# SkyKontrol-powerMeter.net
KiCad netlist of a schematic drawn in EAGLE
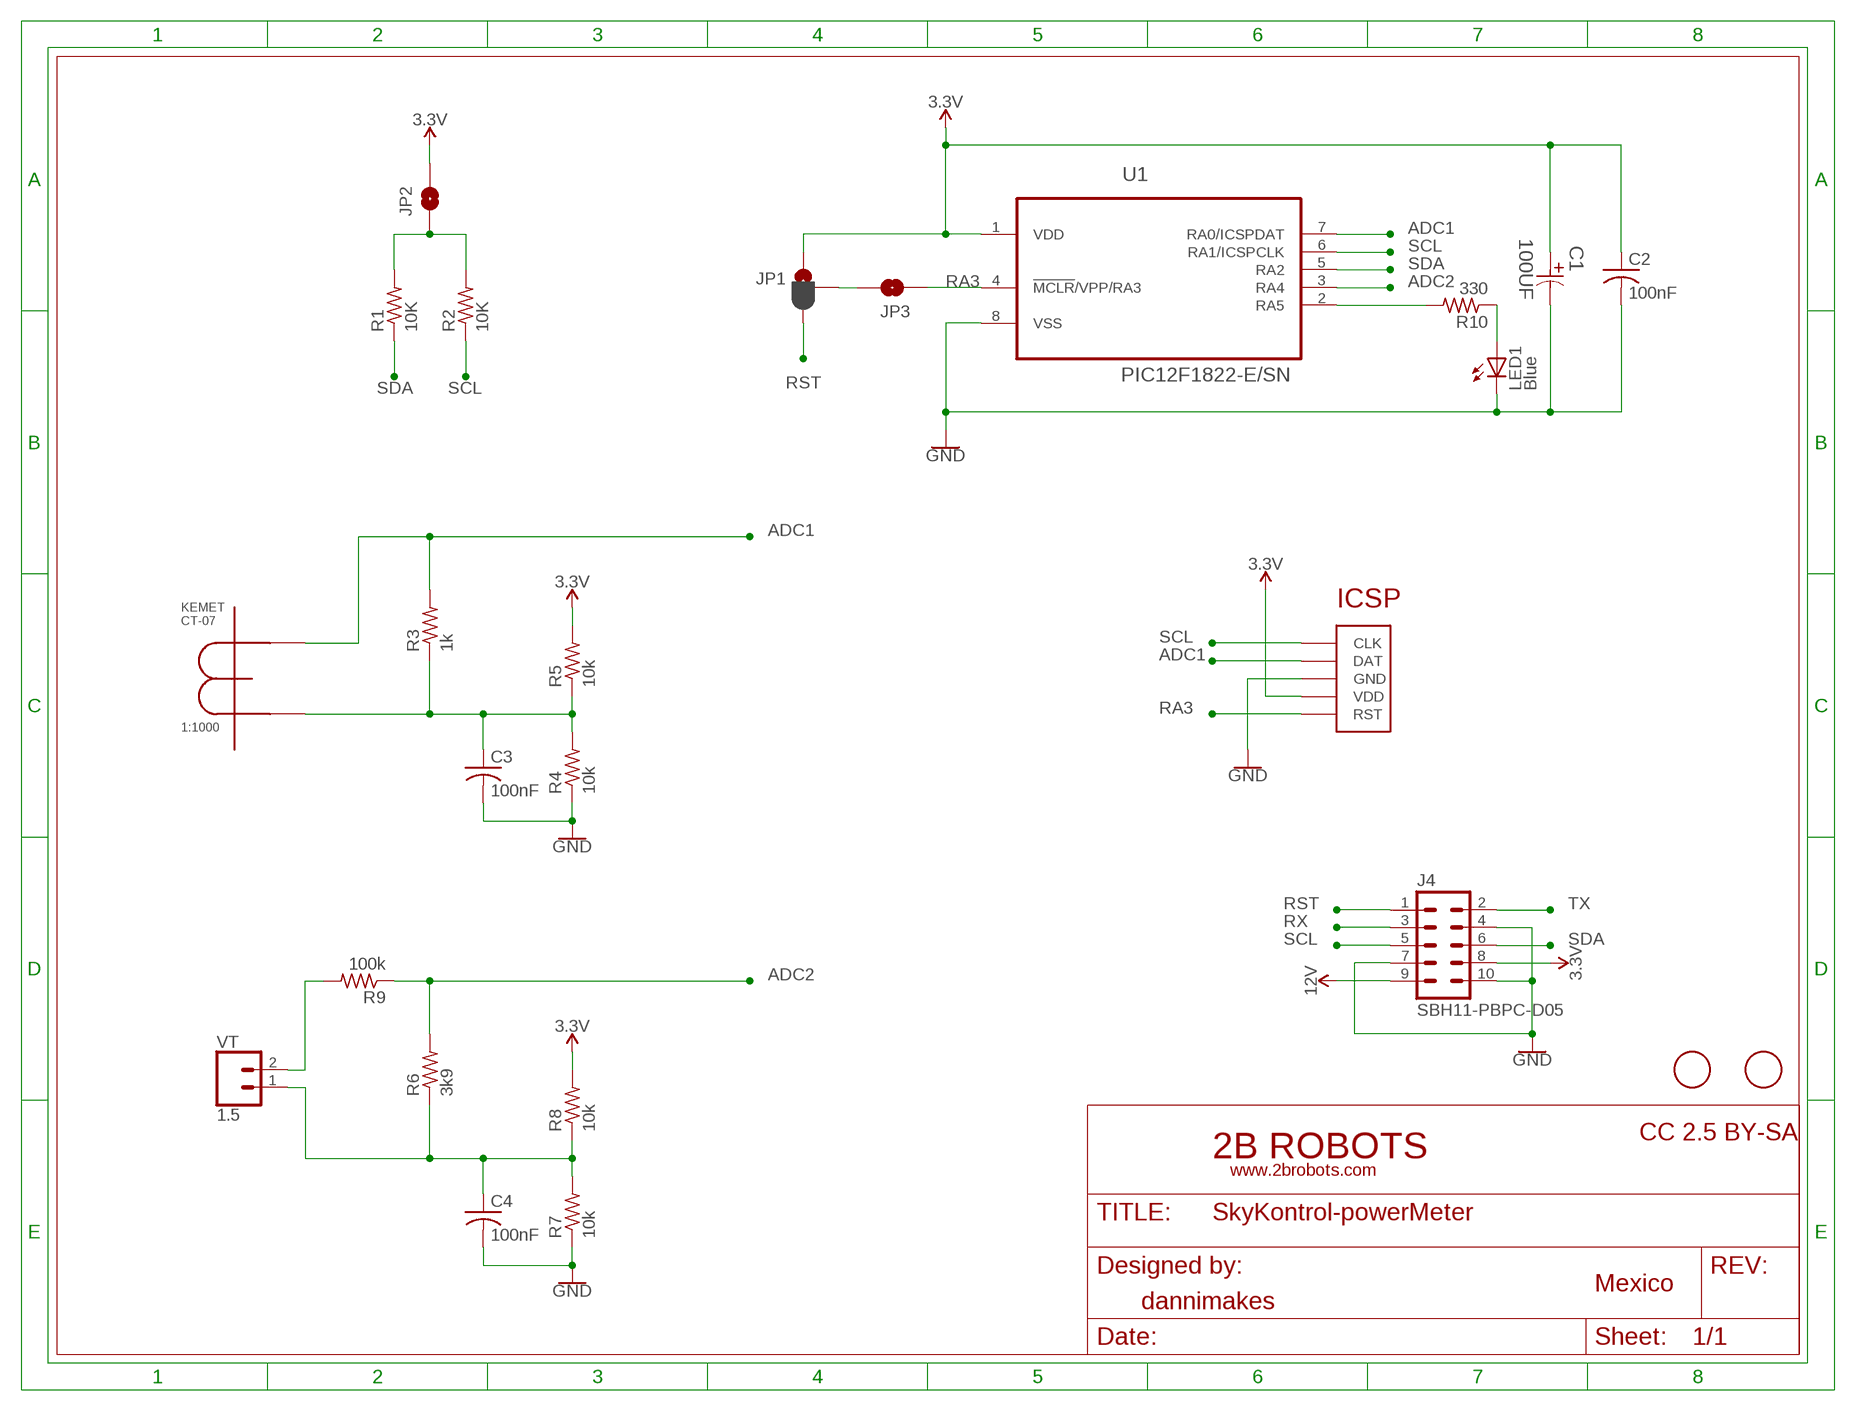
[diagram p0: schematic, sheet 1]

(export (version "E")
  (design (tool "Eeschema 10.0.6"))
  (components
    (comp (ref "C1")
      (value "100UF")
      (footprint "eagle-import:CAPAE660X800N")
      (fields (field (name "MPN") "EEE-HA1E101XP") (field (name "TOLERANCE") "±20 %"))
      (libsource (lib "eagle-import") (part "EEE--CASE-D8HA1E101XP"))
    )
    (comp (ref "C2")
      (value "100nF")
      (footprint "eagle-import:C0603K")
      (libsource (lib "eagle-import") (part "C-USC0603K"))
    )
    (comp (ref "C3")
      (value "100nF")
      (footprint "eagle-import:C0603K")
      (libsource (lib "eagle-import") (part "C-USC0603K"))
    )
    (comp (ref "C4")
      (value "100nF")
      (footprint "eagle-import:C0603K")
      (libsource (lib "eagle-import") (part "C-USC0603K"))
    )
    (comp (ref "J4")
      (value "SBH11-PBPC-D05")
      (footprint "eagle-import:SBH11-PBPC-D05")
      (libsource (lib "eagle-import") (part "SBH11-PBPC-D05"))
    )
    (comp (ref "JP1")
      (value "JUMPER-SMT_3_1-NC_PASTE_SILK")
      (footprint "eagle-import:SMT-JUMPER_3_1-NC_PASTE_SILK")
      (libsource (lib "eagle-import") (part "JUMPER-SMT_3_1-NC_PASTE_SILK"))
    )
    (comp (ref "JP2")
      (value "JUMPER-SMT_2_NO_SILK")
      (footprint "eagle-import:SMT-JUMPER_2_NO_SILK")
      (libsource (lib "eagle-import") (part "JUMPER-SMT_2_NO_SILK"))
    )
    (comp (ref "JP3")
      (value "JUMPER-SMT_2_NO_SILK")
      (footprint "eagle-import:SMT-JUMPER_2_NO_SILK")
      (libsource (lib "eagle-import") (part "JUMPER-SMT_2_NO_SILK"))
    )
    (comp (ref "LED1")
      (value "Blue")
      (footprint "eagle-import:CHIPLED_1206")
      (libsource (lib "eagle-import") (part "LEDCHIPLED_1206"))
    )
    (comp (ref "R1")
      (value "10K")
      (footprint "eagle-import:R0805")
      (libsource (lib "eagle-import") (part "R-US_R0805"))
    )
    (comp (ref "R2")
      (value "10K")
      (footprint "eagle-import:R0805")
      (libsource (lib "eagle-import") (part "R-US_R0805"))
    )
    (comp (ref "R3")
      (value "1k")
      (footprint "eagle-import:R0805")
      (libsource (lib "eagle-import") (part "R-US_R0805"))
    )
    (comp (ref "R4")
      (value "10k")
      (footprint "eagle-import:R0805")
      (libsource (lib "eagle-import") (part "R-US_R0805"))
    )
    (comp (ref "R5")
      (value "10k")
      (footprint "eagle-import:R0805")
      (libsource (lib "eagle-import") (part "R-US_R0805"))
    )
    (comp (ref "R6")
      (value "3k9")
      (footprint "eagle-import:R0805")
      (libsource (lib "eagle-import") (part "R-US_R0805"))
    )
    (comp (ref "R7")
      (value "10k")
      (footprint "eagle-import:R0805")
      (libsource (lib "eagle-import") (part "R-US_R0805"))
    )
    (comp (ref "R8")
      (value "10k")
      (footprint "eagle-import:R0805")
      (libsource (lib "eagle-import") (part "R-US_R0805"))
    )
    (comp (ref "R9")
      (value "100k")
      (footprint "eagle-import:R0805")
      (libsource (lib "eagle-import") (part "R-US_R0805"))
    )
    (comp (ref "R10")
      (value "330")
      (footprint "eagle-import:R0805")
      (libsource (lib "eagle-import") (part "R-US_R0805"))
    )
    (comp (ref "U$1")
      (value "FIDUCIAL")
      (footprint "eagle-import:FIDUCIAL_1MM")
      (libsource (lib "eagle-import") (part "FIDUCIAL"))
    )
    (comp (ref "U$2")
      (value "ICSP_POGO")
      (footprint "eagle-import:ICSP_POGO")
      (libsource (lib "eagle-import") (part "ICSP_POGO"))
    )
    (comp (ref "U$3")
      (value "FIDUCIAL")
      (footprint "eagle-import:FIDUCIAL_1MM")
      (libsource (lib "eagle-import") (part "FIDUCIAL"))
    )
    (comp (ref "U$4")
      (value "CT-07KEMET")
      (footprint "eagle-import:CT-07")
      (libsource (lib "eagle-import") (part "CT-07KEMET"))
    )
    (comp (ref "U1")
      (value "PIC12F1822-E/SN")
      (footprint "eagle-import:SOIC127P600X175-8N")
      (libsource (lib "eagle-import") (part "PIC12F1822-E/SN"))
    )
    (comp (ref "VT")
      (value "1.5")
      (footprint "eagle-import:SCREWTERMINAL-5MM-2")
      (libsource (lib "eagle-import") (part "CONN_025MM"))
    )
  )
  (nets
    (net (code "1") (name "/ADC1") (class "Default")
      (node (ref "R3") (pin "2") (pinfunction "2_2") (pintype "passive"))
      (node (ref "U$2") (pin "P$4") (pinfunction "DAT_P$4") (pintype "bidirectional"))
      (node (ref "U$4") (pin "P$1") (pinfunction "C1_P$1") (pintype "bidirectional"))
      (node (ref "U1") (pin "7") (pinfunction "RA0/ICSPDAT_7") (pintype "bidirectional"))
    )
    (net (code "2") (name "/ADC2") (class "Default")
      (node (ref "R6") (pin "2") (pinfunction "2_2") (pintype "passive"))
      (node (ref "R9") (pin "1") (pinfunction "1_1") (pintype "passive"))
      (node (ref "U1") (pin "3") (pinfunction "RA4_3") (pintype "bidirectional"))
    )
    (net (code "3") (name "/RA3") (class "Default")
      (node (ref "JP3") (pin "1") (pinfunction "1_1") (pintype "passive"))
      (node (ref "U$2") (pin "P$1") (pinfunction "RST_P$1") (pintype "bidirectional"))
      (node (ref "U1") (pin "4") (pinfunction "~{MCLR}/VPP/RA3_4") (pintype "input"))
    )
    (net (code "4") (name "/RST") (class "Default")
      (node (ref "J4") (pin "1") (pinfunction "1_1") (pintype "passive"))
      (node (ref "JP1") (pin "3") (pinfunction "3_3") (pintype "passive"))
    )
    (net (code "5") (name "/RX") (class "Default")
      (node (ref "J4") (pin "3") (pinfunction "3_3") (pintype "passive"))
    )
    (net (code "6") (name "/SCL") (class "Default")
      (node (ref "J4") (pin "5") (pinfunction "5_5") (pintype "passive"))
      (node (ref "R2") (pin "1") (pinfunction "1_1") (pintype "passive"))
      (node (ref "U$2") (pin "P$5") (pinfunction "CLK_P$5") (pintype "bidirectional"))
      (node (ref "U1") (pin "6") (pinfunction "RA1/ICSPCLK_6") (pintype "bidirectional"))
    )
    (net (code "7") (name "/SDA") (class "Default")
      (node (ref "J4") (pin "6") (pinfunction "6_6") (pintype "passive"))
      (node (ref "R1") (pin "1") (pinfunction "1_1") (pintype "passive"))
      (node (ref "U1") (pin "5") (pinfunction "RA2_5") (pintype "bidirectional"))
    )
    (net (code "8") (name "/TX") (class "Default")
      (node (ref "J4") (pin "2") (pinfunction "2_2") (pintype "passive"))
    )
    (net (code "9") (name "3.3V") (class "Default")
      (node (ref "C1") (pin "1") (pinfunction "1_1") (pintype "passive"))
      (node (ref "C2") (pin "1") (pinfunction "1_1") (pintype "passive"))
      (node (ref "J4") (pin "8") (pinfunction "8_8") (pintype "passive"))
      (node (ref "JP1") (pin "1") (pinfunction "1_1") (pintype "passive"))
      (node (ref "JP2") (pin "2") (pinfunction "2_2") (pintype "passive"))
      (node (ref "R5") (pin "2") (pinfunction "2_2") (pintype "passive"))
      (node (ref "R8") (pin "2") (pinfunction "2_2") (pintype "passive"))
      (node (ref "U$2") (pin "P$2") (pinfunction "VDD_P$2") (pintype "bidirectional"))
      (node (ref "U1") (pin "1") (pinfunction "VDD_1") (pintype "power_in"))
    )
    (net (code "10") (name "12V") (class "Default")
      (node (ref "J4") (pin "9") (pinfunction "9_9") (pintype "passive"))
    )
    (net (code "11") (name "GND") (class "Default")
      (node (ref "C1") (pin "2") (pinfunction "2_2") (pintype "passive"))
      (node (ref "C2") (pin "2") (pinfunction "2_2") (pintype "passive"))
      (node (ref "C3") (pin "2") (pinfunction "2_2") (pintype "passive"))
      (node (ref "C4") (pin "2") (pinfunction "2_2") (pintype "passive"))
      (node (ref "J4") (pin "10") (pinfunction "10_10") (pintype "passive"))
      (node (ref "J4") (pin "4") (pinfunction "4_4") (pintype "passive"))
      (node (ref "J4") (pin "7") (pinfunction "7_7") (pintype "passive"))
      (node (ref "LED1") (pin "C") (pinfunction "C_C") (pintype "passive"))
      (node (ref "R4") (pin "1") (pinfunction "1_1") (pintype "passive"))
      (node (ref "R7") (pin "1") (pinfunction "1_1") (pintype "passive"))
      (node (ref "U$2") (pin "P$3") (pinfunction "GND_P$3") (pintype "bidirectional"))
      (node (ref "U1") (pin "8") (pinfunction "VSS_8") (pintype "power_in"))
    )
    (net (code "12") (name "Net-(C4-Pad1)") (class "Default")
      (node (ref "C4") (pin "1") (pinfunction "1_1") (pintype "passive"))
      (node (ref "R6") (pin "1") (pinfunction "1_1") (pintype "passive"))
      (node (ref "R7") (pin "2") (pinfunction "2_2") (pintype "passive"))
      (node (ref "R8") (pin "1") (pinfunction "1_1") (pintype "passive"))
      (node (ref "VT") (pin "1") (pinfunction "1_1") (pintype "passive"))
    )
    (net (code "13") (name "Net-(JP1-Pad2)") (class "Default")
      (node (ref "JP1") (pin "2") (pinfunction "2_2") (pintype "passive"))
      (node (ref "JP3") (pin "2") (pinfunction "2_2") (pintype "passive"))
    )
    (net (code "14") (name "Net-(JP2-Pad1)") (class "Default")
      (node (ref "JP2") (pin "1") (pinfunction "1_1") (pintype "passive"))
      (node (ref "R1") (pin "2") (pinfunction "2_2") (pintype "passive"))
      (node (ref "R2") (pin "2") (pinfunction "2_2") (pintype "passive"))
    )
    (net (code "15") (name "Net-(LED1-PadA)") (class "Default")
      (node (ref "LED1") (pin "A") (pinfunction "A_A") (pintype "passive"))
      (node (ref "R10") (pin "1") (pinfunction "1_1") (pintype "passive"))
    )
    (net (code "16") (name "Net-(R9-Pad2)") (class "Default")
      (node (ref "R9") (pin "2") (pinfunction "2_2") (pintype "passive"))
      (node (ref "VT") (pin "2") (pinfunction "2_2") (pintype "passive"))
    )
    (net (code "17") (name "Net-(U$4-C2)") (class "Default")
      (node (ref "C3") (pin "1") (pinfunction "1_1") (pintype "passive"))
      (node (ref "R3") (pin "1") (pinfunction "1_1") (pintype "passive"))
      (node (ref "R4") (pin "2") (pinfunction "2_2") (pintype "passive"))
      (node (ref "R5") (pin "1") (pinfunction "1_1") (pintype "passive"))
      (node (ref "U$4") (pin "P$2") (pinfunction "C2_P$2") (pintype "bidirectional"))
    )
    (net (code "18") (name "Net-(U1-RA5)") (class "Default")
      (node (ref "R10") (pin "2") (pinfunction "2_2") (pintype "passive"))
      (node (ref "U1") (pin "2") (pinfunction "RA5_2") (pintype "bidirectional"))
    )
  )
)
